# Battery.net
KiCad netlist of a schematic drawn in Altium Designer
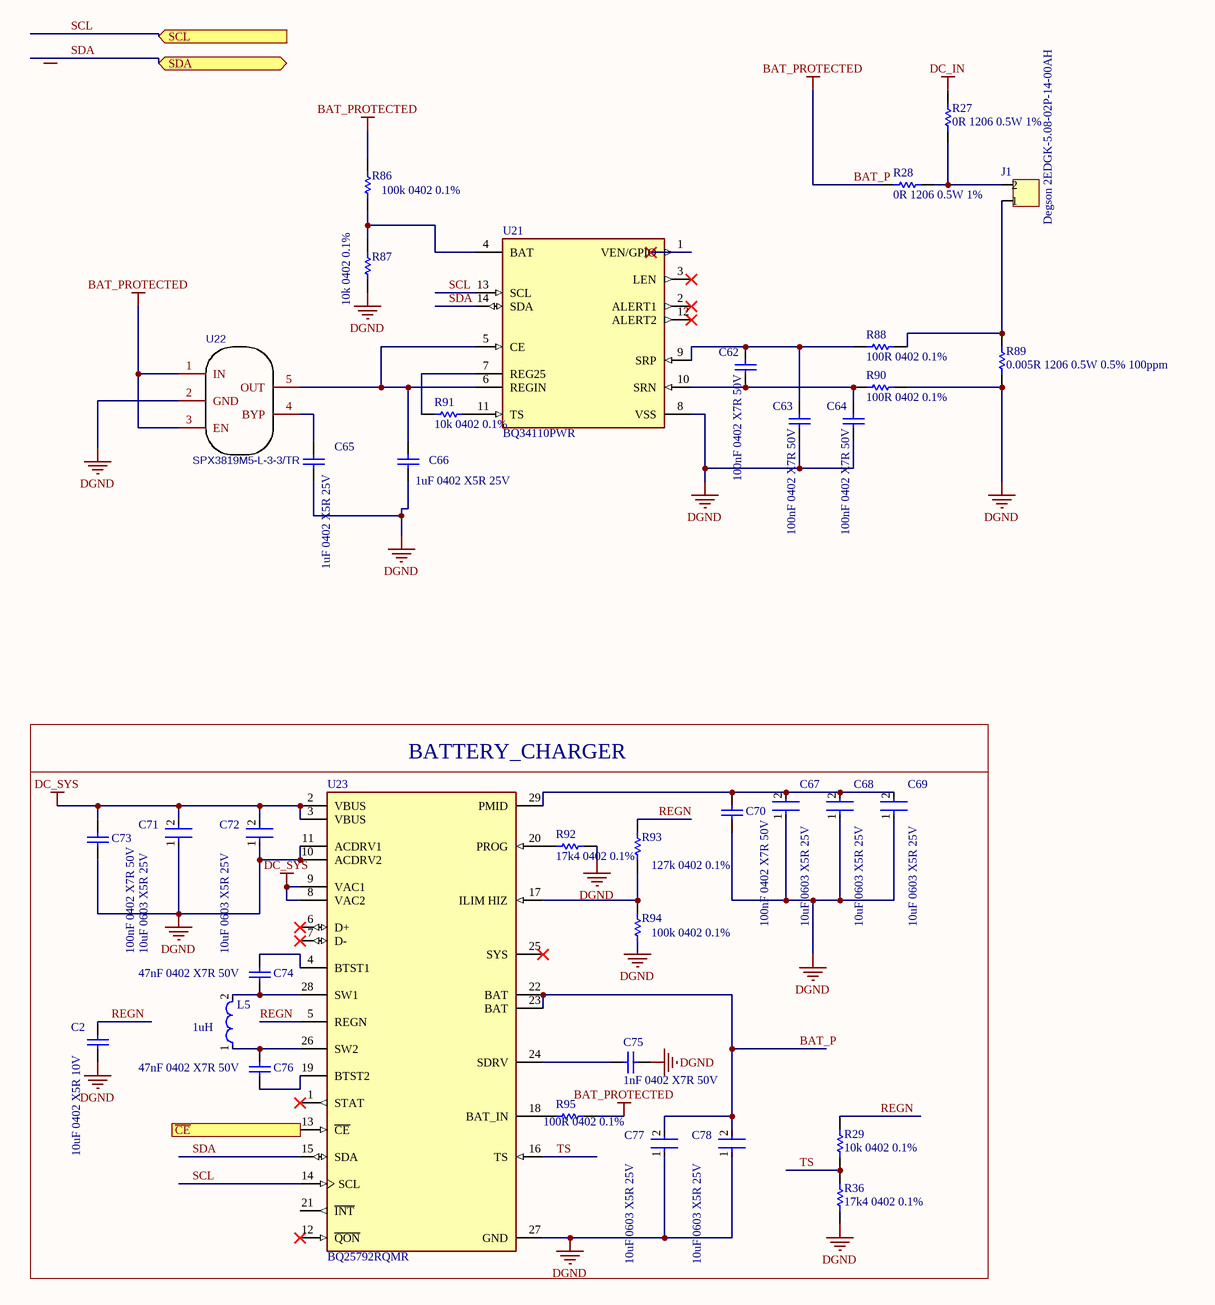
[diagram p0: Battery.SchDoc]

(export (version "E")
  (design (tool "Eeschema 10.0.6"))
  (components
    (comp (ref "C2")
      (value "10uF 0402 X5R 10V")
      (footprint "CAPC1005X55X25NL5T10")
      (libsource (lib "Altium Content Vault") (part "CAP-NP-2"))
    )
    (comp (ref "C62")
      (value "100nF 0402 X7R 50V")
      (footprint "CAPC1005X55X25NL5T10")
      (libsource (lib "Altium Content Vault") (part "CAP-NP-2"))
    )
    (comp (ref "C63")
      (value "100nF 0402 X7R 50V")
      (footprint "CAPC1005X55X25NL5T10")
      (libsource (lib "Altium Content Vault") (part "CAP-NP-2"))
    )
    (comp (ref "C64")
      (value "100nF 0402 X7R 50V")
      (footprint "CAPC1005X55X25NL5T10")
      (libsource (lib "Altium Content Vault") (part "CAP-NP-2"))
    )
    (comp (ref "C65")
      (value "1uF 0402 X5R 25V")
      (footprint "CAPC1005X55X25NL5T10")
      (libsource (lib "Altium Content Vault") (part "CAP-NP-2"))
    )
    (comp (ref "C66")
      (value "1uF 0402 X5R 25V")
      (footprint "CAPC1005X55X25NL5T10")
      (libsource (lib "Altium Content Vault") (part "CAP-NP-2"))
    )
    (comp (ref "C67")
      (value "10uF 0603 X5R 25V")
      (footprint "FP-GRM188-0_2-IPC_B")
      (libsource (lib "Altium Content Vault") (part "11868f565c42a9108669ba33697ecf6"))
    )
    (comp (ref "C68")
      (value "10uF 0603 X5R 25V")
      (footprint "FP-GRM188-0_2-IPC_B")
      (libsource (lib "Altium Content Vault") (part "11868f565c42a9108669ba33697ecf6"))
    )
    (comp (ref "C69")
      (value "10uF 0603 X5R 25V")
      (footprint "FP-GRM188-0_2-IPC_B")
      (libsource (lib "Altium Content Vault") (part "11868f565c42a9108669ba33697ecf6"))
    )
    (comp (ref "C70")
      (value "100nF 0402 X7R 50V")
      (footprint "CAPC1005X55X25NL5T10")
      (libsource (lib "Altium Content Vault") (part "CAP-NP-2"))
    )
    (comp (ref "C71")
      (value "10uF 0603 X5R 25V")
      (footprint "FP-GRM188-0_2-IPC_B")
      (libsource (lib "Altium Content Vault") (part "11868f565c42a9108669ba33697ecf6"))
    )
    (comp (ref "C72")
      (value "10uF 0603 X5R 25V")
      (footprint "FP-GRM188-0_2-IPC_B")
      (libsource (lib "Altium Content Vault") (part "11868f565c42a9108669ba33697ecf6"))
    )
    (comp (ref "C73")
      (value "100nF 0402 X7R 50V")
      (footprint "CAPC1005X55X25NL5T10")
      (libsource (lib "Altium Content Vault") (part "CAP-NP-2"))
    )
    (comp (ref "C74")
      (value "47nF 0402 X7R 50V")
      (footprint "CAPC1005X55X25NL5T10")
      (libsource (lib "Altium Content Vault") (part "CAP-NP-2"))
    )
    (comp (ref "C75")
      (value "1nF 0402 X7R 50V")
      (footprint "CAPC1005X55X25NL5T10")
      (libsource (lib "Altium Content Vault") (part "CAP-NP-2"))
    )
    (comp (ref "C76")
      (value "47nF 0402 X7R 50V")
      (footprint "CAPC1005X55X25NL5T10")
      (libsource (lib "Altium Content Vault") (part "CAP-NP-2"))
    )
    (comp (ref "C77")
      (value "10uF 0603 X5R 25V")
      (footprint "FP-GRM188-0_2-IPC_B")
      (libsource (lib "Altium Content Vault") (part "11868f565c42a9108669ba33697ecf6"))
    )
    (comp (ref "C78")
      (value "10uF 0603 X5R 25V")
      (footprint "FP-GRM188-0_2-IPC_B")
      (libsource (lib "Altium Content Vault") (part "11868f565c42a9108669ba33697ecf6"))
    )
    (comp (ref "J1")
      (value "Degson 2EDGK-5.08-02P-14-00AH")
      (footprint "PCB-h4cyb3wxd4gf7j132tzl-1")
      (description "Terminal block, 5mm 2 Pos, through hole male.")
      (fields
        (field (name "MANUFACTURER PART NUMBER") "2EDGK-5.08-02P-14-00AH + 2EDGVC-5.08-02P")
        (field (name "LCSC PART") "C8445")
      )
      (libsource (lib "in3ator") (part "CMP-7a42b7ee166ba585-1"))
    )
    (comp (ref "L5")
      (value "DFE201612E-1R0M=P2")
      (footprint "FP-DFE201612C-IPC_A")
      (description "Shielded Wirewound Inductor 1uH 20% 2900mA 0.048Ω 0806 (2016)")
      (fields (field (name "INDUCTANCE") "1uH"))
      (libsource (lib "Altium Content Vault") (part "725321dda6339637d4d059423bc1c3c"))
    )
    (comp (ref "R27")
      (value "0R 1206 0.5W 1%")
      (footprint "CAPC3216X180X55ML20T25")
      (fields (field (name "MANUFACTURER PART NUMBER") "WSLP12065L000FEA") (field (name "POWER") "1W"))
      (libsource (lib "in3ator") (part "CMP-0abdc173b10ad57a-1"))
    )
    (comp (ref "R28")
      (value "0R 1206 0.5W 1%")
      (footprint "CAPC3216X180X55ML20T25")
      (fields (field (name "MANUFACTURER PART NUMBER") "WSLP12065L000FEA") (field (name "POWER") "1W"))
      (libsource (lib "in3ator") (part "CMP-0abdc173b10ad57a-1"))
    )
    (comp (ref "R29")
      (value "10k 0402 0.1%")
      (footprint "RESC1005X40X25ML05T10")
      (libsource (lib "Altium Content Vault") (part "RES"))
    )
    (comp (ref "R36")
      (value "17k4 0402 0.1%")
      (footprint "RESC1005X40X25ML05T10")
      (libsource (lib "Altium Content Vault") (part "RES"))
    )
    (comp (ref "R86")
      (value "100k 0402 0.1%")
      (footprint "RESC1005X40X25ML05T10")
      (libsource (lib "Altium Content Vault") (part "RES"))
    )
    (comp (ref "R87")
      (value "10k 0402 0.1%")
      (footprint "RESC1005X40X25ML05T10")
      (libsource (lib "Altium Content Vault") (part "RES"))
    )
    (comp (ref "R88")
      (value "100R 0402 0.1%")
      (footprint "RESC1005X40X25ML05T10")
      (libsource (lib "Altium Content Vault") (part "RES"))
    )
    (comp (ref "R89")
      (value "0.005R 1206 0.5W 0.5% 100ppm")
      (footprint "CAPC3216X180X55ML20T25")
      (description "0.002R 1206 0.5W 1%")
      (fields (field (name "MANUFACTURER PART NUMBER") "WSLP12065L000FEA") (field (name "POWER") "1W"))
      (libsource (lib "in3ator") (part "CMP-0abdc173b10ad57a-1"))
    )
    (comp (ref "R90")
      (value "100R 0402 0.1%")
      (footprint "RESC1005X40X25ML05T10")
      (libsource (lib "Altium Content Vault") (part "RES"))
    )
    (comp (ref "R91")
      (value "10k 0402 0.1%")
      (footprint "RESC1005X40X25ML05T10")
      (libsource (lib "Altium Content Vault") (part "RES"))
    )
    (comp (ref "R92")
      (value "17k4 0402 0.1%")
      (footprint "RESC1005X40X25ML05T10")
      (libsource (lib "Altium Content Vault") (part "RES"))
    )
    (comp (ref "R93")
      (value "127k 0402 0.1%")
      (footprint "RESC1005X40X25ML05T10")
      (libsource (lib "Altium Content Vault") (part "RES"))
    )
    (comp (ref "R94")
      (value "100k 0402 0.1%")
      (footprint "RESC1005X40X25ML05T10")
      (libsource (lib "Altium Content Vault") (part "RES"))
    )
    (comp (ref "R95")
      (value "100R 0402 0.1%")
      (footprint "RESC1005X40X25ML05T10")
      (libsource (lib "Altium Content Vault") (part "RES"))
    )
    (comp (ref "U21")
      (value "BQ34110PWR")
      (footprint "FP-PW0014A-MFG")
      (description "IC BATT MON MULTICELL 14TSSOP")
      (fields
        (field (name "MANUFACTURER") "Texas Instruments")
        (field (name "OCTOPART") "https://octopart.com/bq34110pwr-texas+instruments-75529711")
      )
      (libsource (lib "Altium Content Vault") (part "b2e9668674e0459d52d848cff3a60af"))
    )
    (comp (ref "U22")
      (value "SPX3819M5-L-3-3/TR")
      (footprint "SOT-23-5_L3.0-W1.7-P0.95-LS2.8-BR")
      (fields (field (name "BOM_SUPPLIER PART") "C9055"))
      (libsource (lib "LCSC") (part "SPX3819M5-L-3-3/TR"))
    )
    (comp (ref "U23")
      (value "BQ25792RQMR")
      (footprint "FP-RQM0029A-MFG")
      (description "I2C CONTROLLED, 5-A, 1-4 CELL BU")
      (libsource (lib "Altium Content Vault") (part "43137d39c585c4e49e3b8f41bbae565"))
    )
  )
  (nets
    (net (code "1") (name "/REGN") (class "Default")
      (node (ref "C2") (pin "2") (pinfunction "2_2") (pintype "passive"))
      (node (ref "R29") (pin "1") (pinfunction "1_1") (pintype "passive"))
      (node (ref "R93") (pin "2") (pinfunction "2_2") (pintype "passive"))
      (node (ref "U23") (pin "5") (pinfunction "REGN_5") (pintype "power_in"))
    )
    (net (code "2") (name "/SCL") (class "Default")
      (node (ref "U21") (pin "13") (pinfunction "SCL_13") (pintype "input"))
      (node (ref "U23") (pin "14") (pinfunction "SCL_14") (pintype "input"))
    )
    (net (code "3") (name "/SDA") (class "Default")
      (node (ref "U21") (pin "14") (pinfunction "SDA_14") (pintype "bidirectional"))
      (node (ref "U23") (pin "15") (pinfunction "SDA_15") (pintype "bidirectional"))
    )
    (net (code "4") (name "/TS") (class "Default")
      (node (ref "R29") (pin "2") (pinfunction "2_2") (pintype "passive"))
      (node (ref "R36") (pin "1") (pinfunction "1_1") (pintype "passive"))
      (node (ref "U23") (pin "16") (pinfunction "TS_16") (pintype "input"))
    )
    (net (code "5") (name "/~{CE}") (class "Default")
      (node (ref "U23") (pin "13") (pinfunction "~{CE}_13") (pintype "input"))
    )
    (net (code "6") (name "BAT_PROTECTED") (class "Default")
      (node (ref "C77") (pin "2") (pinfunction "2_2") (pintype "passive"))
      (node (ref "C78") (pin "2") (pinfunction "2_2") (pintype "passive"))
      (node (ref "R28") (pin "1") (pinfunction "1_1") (pintype "passive"))
      (node (ref "R86") (pin "2") (pinfunction "2_2") (pintype "passive"))
      (node (ref "R95") (pin "1") (pinfunction "1_1") (pintype "passive"))
      (node (ref "U22") (pin "1") (pinfunction "IN_1") (pintype "passive"))
      (node (ref "U22") (pin "3") (pinfunction "EN_3") (pintype "passive"))
      (node (ref "U23") (pin "22") (pinfunction "BAT_22") (pintype "power_in"))
      (node (ref "U23") (pin "23") (pinfunction "BAT_23") (pintype "power_in"))
    )
    (net (code "7") (name "DC_IN") (class "Default")
      (node (ref "R27") (pin "1") (pinfunction "1_1") (pintype "passive"))
    )
    (net (code "8") (name "DC_SYS") (class "Default")
      (node (ref "C71") (pin "2") (pinfunction "2_2") (pintype "passive"))
      (node (ref "C72") (pin "2") (pinfunction "2_2") (pintype "passive"))
      (node (ref "C73") (pin "2") (pinfunction "2_2") (pintype "passive"))
      (node (ref "U23") (pin "2") (pinfunction "VBUS_2") (pintype "power_in"))
      (node (ref "U23") (pin "3") (pinfunction "VBUS_3") (pintype "power_in"))
      (node (ref "U23") (pin "8") (pinfunction "VAC2_8") (pintype "power_in"))
      (node (ref "U23") (pin "9") (pinfunction "VAC1_9") (pintype "power_in"))
    )
    (net (code "9") (name "DGND") (class "Default")
      (node (ref "C2") (pin "1") (pinfunction "1_1") (pintype "passive"))
      (node (ref "C63") (pin "1") (pinfunction "1_1") (pintype "passive"))
      (node (ref "C64") (pin "1") (pinfunction "1_1") (pintype "passive"))
      (node (ref "C65") (pin "1") (pinfunction "1_1") (pintype "passive"))
      (node (ref "C66") (pin "1") (pinfunction "1_1") (pintype "passive"))
      (node (ref "C67") (pin "1") (pinfunction "1_1") (pintype "passive"))
      (node (ref "C68") (pin "1") (pinfunction "1_1") (pintype "passive"))
      (node (ref "C69") (pin "1") (pinfunction "1_1") (pintype "passive"))
      (node (ref "C70") (pin "1") (pinfunction "1_1") (pintype "passive"))
      (node (ref "C71") (pin "1") (pinfunction "1_1") (pintype "passive"))
      (node (ref "C72") (pin "1") (pinfunction "1_1") (pintype "passive"))
      (node (ref "C73") (pin "1") (pinfunction "1_1") (pintype "passive"))
      (node (ref "C75") (pin "1") (pinfunction "1_1") (pintype "passive"))
      (node (ref "C77") (pin "1") (pinfunction "1_1") (pintype "passive"))
      (node (ref "C78") (pin "1") (pinfunction "1_1") (pintype "passive"))
      (node (ref "R36") (pin "2") (pinfunction "2_2") (pintype "passive"))
      (node (ref "R87") (pin "1") (pinfunction "1_1") (pintype "passive"))
      (node (ref "R89") (pin "2") (pinfunction "2_2") (pintype "passive"))
      (node (ref "R90") (pin "1") (pinfunction "1_1") (pintype "passive"))
      (node (ref "R92") (pin "1") (pinfunction "1_1") (pintype "passive"))
      (node (ref "R94") (pin "1") (pinfunction "1_1") (pintype "passive"))
      (node (ref "U21") (pin "8") (pinfunction "VSS_8") (pintype "power_in"))
      (node (ref "U22") (pin "2") (pinfunction "GND_2") (pintype "passive"))
      (node (ref "U23") (pin "10") (pinfunction "ACDRV2_10") (pintype "power_in"))
      (node (ref "U23") (pin "11") (pinfunction "ACDRV1_11") (pintype "power_in"))
      (node (ref "U23") (pin "27") (pinfunction "GND_27") (pintype "power_in"))
    )
    (net (code "10") (name "Net-(J1-Pad1)") (class "Default")
      (node (ref "J1") (pin "1") (pinfunction "1_1") (pintype "passive"))
      (node (ref "R88") (pin "1") (pinfunction "1_1") (pintype "passive"))
      (node (ref "R89") (pin "1") (pinfunction "1_1") (pintype "passive"))
    )
    (net (code "11") (name "Net-(J1-Pad2)") (class "Default")
      (node (ref "J1") (pin "2") (pinfunction "2_2") (pintype "passive"))
      (node (ref "R27") (pin "2") (pinfunction "2_2") (pintype "passive"))
      (node (ref "R28") (pin "2") (pinfunction "2_2") (pintype "passive"))
    )
    (net (code "12") (name "Net-(U21-BAT)") (class "Default")
      (node (ref "R86") (pin "1") (pinfunction "1_1") (pintype "passive"))
      (node (ref "R87") (pin "2") (pinfunction "2_2") (pintype "passive"))
      (node (ref "U21") (pin "4") (pinfunction "BAT_4") (pintype "power_in"))
    )
    (net (code "13") (name "Net-(U21-CE)") (class "Default")
      (node (ref "C66") (pin "2") (pinfunction "2_2") (pintype "passive"))
      (node (ref "U21") (pin "5") (pinfunction "CE_5") (pintype "input"))
      (node (ref "U21") (pin "6") (pinfunction "REGIN_6") (pintype "open_emitter"))
      (node (ref "U22") (pin "5") (pinfunction "OUT_5") (pintype "passive"))
    )
    (net (code "14") (name "Net-(U21-REG25)") (class "Default")
      (node (ref "R91") (pin "2") (pinfunction "2_2") (pintype "passive"))
      (node (ref "U21") (pin "7") (pinfunction "REG25_7") (pintype "power_in"))
    )
    (net (code "15") (name "Net-(U21-SRN)") (class "Default")
      (node (ref "C62") (pin "1") (pinfunction "1_1") (pintype "passive"))
      (node (ref "C64") (pin "2") (pinfunction "2_2") (pintype "passive"))
      (node (ref "R90") (pin "2") (pinfunction "2_2") (pintype "passive"))
      (node (ref "U21") (pin "10") (pinfunction "SRN_10") (pintype "input"))
    )
    (net (code "16") (name "Net-(U21-SRP)") (class "Default")
      (node (ref "C62") (pin "2") (pinfunction "2_2") (pintype "passive"))
      (node (ref "C63") (pin "2") (pinfunction "2_2") (pintype "passive"))
      (node (ref "R88") (pin "2") (pinfunction "2_2") (pintype "passive"))
      (node (ref "U21") (pin "9") (pinfunction "SRP_9") (pintype "input"))
    )
    (net (code "17") (name "Net-(U21-TS)") (class "Default")
      (node (ref "R91") (pin "1") (pinfunction "1_1") (pintype "passive"))
      (node (ref "U21") (pin "11") (pinfunction "TS_11") (pintype "input"))
    )
    (net (code "18") (name "Net-(U22-BYP)") (class "Default")
      (node (ref "C65") (pin "2") (pinfunction "2_2") (pintype "passive"))
      (node (ref "U22") (pin "4") (pinfunction "BYP_4") (pintype "passive"))
    )
    (net (code "19") (name "Net-(U23-BAT_IN)") (class "Default")
      (node (ref "R95") (pin "2") (pinfunction "2_2") (pintype "passive"))
      (node (ref "U23") (pin "18") (pinfunction "BAT_IN_18") (pintype "power_in"))
    )
    (net (code "20") (name "Net-(U23-BTST1)") (class "Default")
      (node (ref "C74") (pin "2") (pinfunction "2_2") (pintype "passive"))
      (node (ref "U23") (pin "4") (pinfunction "BTST1_4") (pintype "power_in"))
    )
    (net (code "21") (name "Net-(U23-BTST2)") (class "Default")
      (node (ref "C76") (pin "1") (pinfunction "1_1") (pintype "passive"))
      (node (ref "U23") (pin "19") (pinfunction "BTST2_19") (pintype "power_in"))
    )
    (net (code "22") (name "Net-(U23-ILIM_HIZ)") (class "Default")
      (node (ref "R93") (pin "1") (pinfunction "1_1") (pintype "passive"))
      (node (ref "R94") (pin "2") (pinfunction "2_2") (pintype "passive"))
      (node (ref "U23") (pin "17") (pinfunction "ILIM_HIZ_17") (pintype "input"))
    )
    (net (code "23") (name "Net-(U23-PMID)") (class "Default")
      (node (ref "C67") (pin "2") (pinfunction "2_2") (pintype "passive"))
      (node (ref "C68") (pin "2") (pinfunction "2_2") (pintype "passive"))
      (node (ref "C69") (pin "2") (pinfunction "2_2") (pintype "passive"))
      (node (ref "C70") (pin "2") (pinfunction "2_2") (pintype "passive"))
      (node (ref "U23") (pin "29") (pinfunction "PMID_29") (pintype "power_in"))
    )
    (net (code "24") (name "Net-(U23-PROG)") (class "Default")
      (node (ref "R92") (pin "2") (pinfunction "2_2") (pintype "passive"))
      (node (ref "U23") (pin "20") (pinfunction "PROG_20") (pintype "input"))
    )
    (net (code "25") (name "Net-(U23-SDRV)") (class "Default")
      (node (ref "C75") (pin "2") (pinfunction "2_2") (pintype "passive"))
      (node (ref "U23") (pin "24") (pinfunction "SDRV_24") (pintype "power_in"))
    )
    (net (code "26") (name "Net-(U23-SW1)") (class "Default")
      (node (ref "C74") (pin "1") (pinfunction "1_1") (pintype "passive"))
      (node (ref "L5") (pin "2") (pinfunction "2_2") (pintype "passive"))
      (node (ref "U23") (pin "28") (pinfunction "SW1_28") (pintype "power_in"))
    )
    (net (code "27") (name "Net-(U23-SW2)") (class "Default")
      (node (ref "C76") (pin "2") (pinfunction "2_2") (pintype "passive"))
      (node (ref "L5") (pin "1") (pinfunction "1_1") (pintype "passive"))
      (node (ref "U23") (pin "26") (pinfunction "SW2_26") (pintype "power_in"))
    )
    (net (code "28") (name "unconnected-(U21-ALERT1-Pad2)") (class "Default")
      (node (ref "U21") (pin "2") (pinfunction "ALERT1_2") (pintype "output+no_connect"))
    )
    (net (code "29") (name "unconnected-(U21-ALERT2-Pad12)") (class "Default")
      (node (ref "U21") (pin "12") (pinfunction "ALERT2_12") (pintype "output+no_connect"))
    )
    (net (code "30") (name "unconnected-(U21-LEN-Pad3)") (class "Default")
      (node (ref "U21") (pin "3") (pinfunction "LEN_3") (pintype "output+no_connect"))
    )
    (net (code "31") (name "unconnected-(U21-VEN{slash}GPIO-Pad1)") (class "Default")
      (node (ref "U21") (pin "1") (pinfunction "VEN/GPIO_1") (pintype "output+no_connect"))
    )
    (net (code "32") (name "unconnected-(U23-D+-Pad6)") (class "Default")
      (node (ref "U23") (pin "6") (pinfunction "D+_6") (pintype "bidirectional+no_connect"))
    )
    (net (code "33") (name "unconnected-(U23-D--Pad7)") (class "Default")
      (node (ref "U23") (pin "7") (pinfunction "D-_7") (pintype "bidirectional+no_connect"))
    )
    (net (code "34") (name "unconnected-(U23-STAT-Pad1)") (class "Default")
      (node (ref "U23") (pin "1") (pinfunction "STAT_1") (pintype "output+no_connect"))
    )
    (net (code "35") (name "unconnected-(U23-SYS-Pad25)") (class "Default")
      (node (ref "U23") (pin "25") (pinfunction "SYS_25") (pintype "power_in+no_connect"))
    )
    (net (code "36") (name "unconnected-(U23-~{INT}-Pad21)") (class "Default")
      (node (ref "U23") (pin "21") (pinfunction "~{INT}_21") (pintype "output"))
    )
    (net (code "37") (name "unconnected-(U23-~{QON}-Pad12)") (class "Default")
      (node (ref "U23") (pin "12") (pinfunction "~{QON}_12") (pintype "input+no_connect"))
    )
  )
)
